# Sheet1.net
KiCad netlist of a schematic drawn in Altium Designer
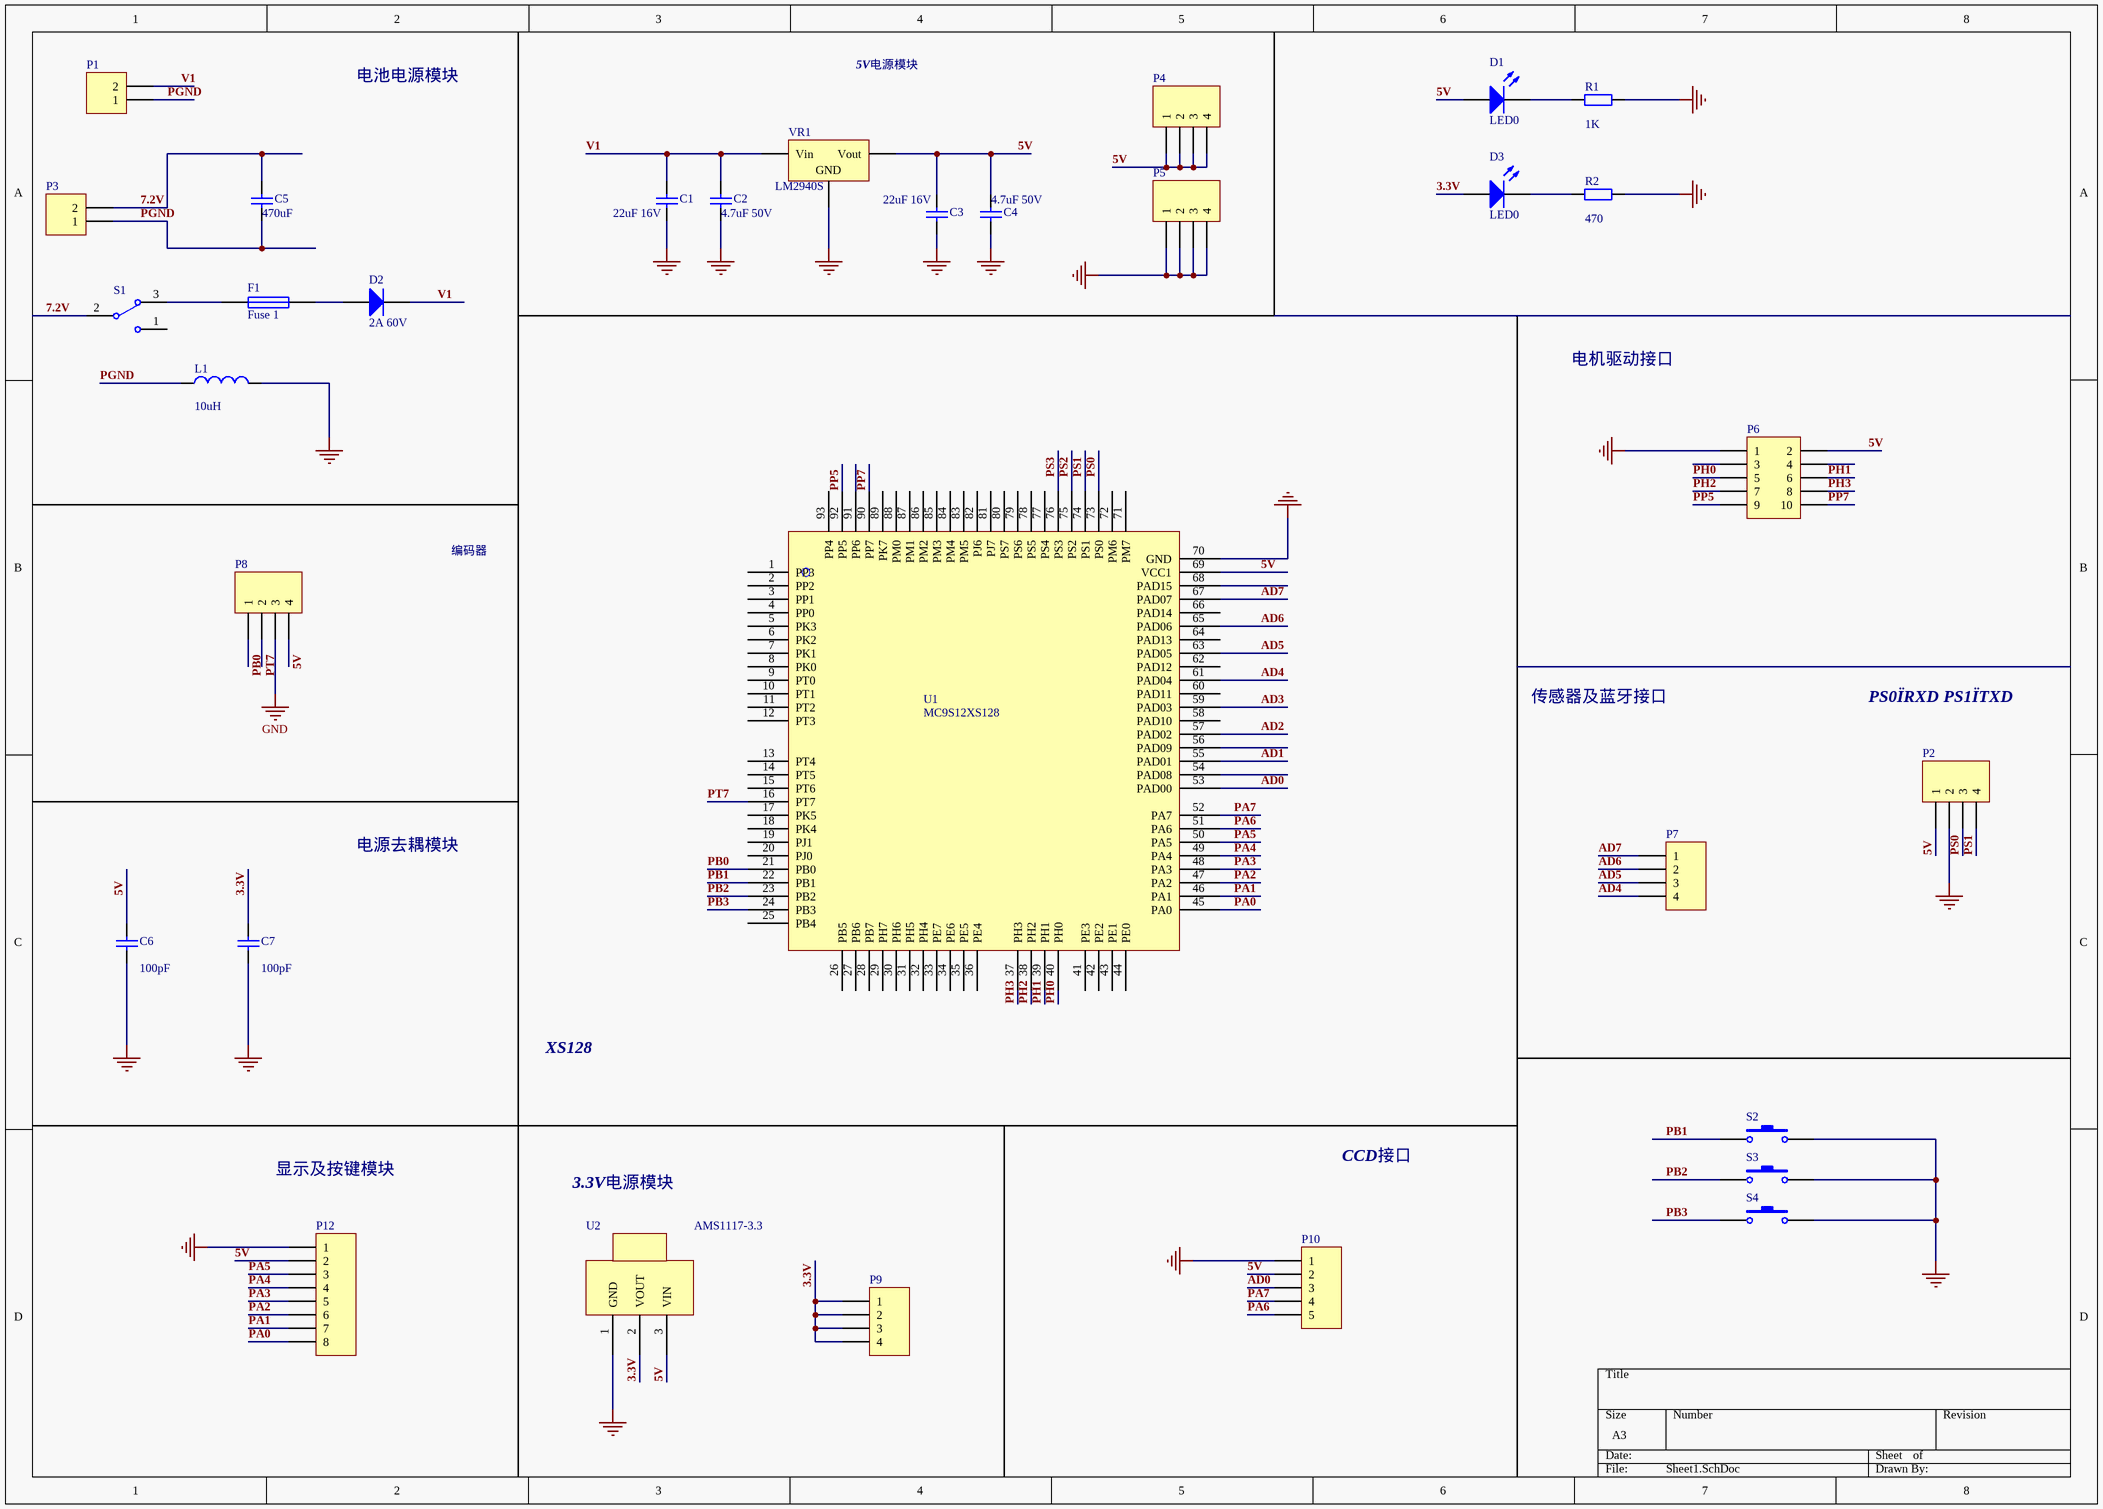
[diagram p0: Sheet1.SchDoc]

(export (version "E")
  (design (tool "Eeschema 10.0.6"))
  (components
    (comp (ref "C1")
      (value "22uF 16V")
      (footprint "22uF钽电容")
      (description "Capacitor")
      (fields (field (name "Comment") "Cap") (field (name "PUBLISHER") "Altium Limited"))
      (libsource (lib "Miscellaneous Devices") (part "Cap"))
    )
    (comp (ref "C2")
      (value "4.7uF 50V")
      (footprint "4.7UF钽电容")
      (description "Capacitor")
      (fields (field (name "Comment") "Cap") (field (name "PUBLISHER") "Altium Limited"))
      (libsource (lib "Miscellaneous Devices") (part "Cap"))
    )
    (comp (ref "C3")
      (value "22uF 16V")
      (footprint "22uF钽电容")
      (description "Capacitor")
      (fields (field (name "Comment") "Cap") (field (name "PUBLISHER") "Altium Limited"))
      (libsource (lib "Miscellaneous Devices") (part "Cap"))
    )
    (comp (ref "C4")
      (value "4.7uF 50V")
      (footprint "4.7UF钽电容")
      (description "Capacitor")
      (fields (field (name "Comment") "Cap") (field (name "PUBLISHER") "Altium Limited"))
      (libsource (lib "Miscellaneous Devices") (part "Cap"))
    )
    (comp (ref "C5")
      (value "470uF")
      (footprint "47UF钽电容")
      (description "Capacitor")
      (fields (field (name "Comment") "Cap") (field (name "PUBLISHER") "Altium Limited"))
      (libsource (lib "Miscellaneous Devices") (part "Cap"))
    )
    (comp (ref "C6")
      (value "100pF")
      (footprint "C0805")
      (description "Capacitor")
      (fields (field (name "Comment") "Cap") (field (name "PUBLISHER") "Altium Limited"))
      (libsource (lib "Miscellaneous Devices") (part "Cap"))
    )
    (comp (ref "C7")
      (value "100pF")
      (footprint "C0805")
      (description "Capacitor")
      (fields (field (name "Comment") "Cap") (field (name "PUBLISHER") "Altium Limited"))
      (libsource (lib "Miscellaneous Devices") (part "Cap"))
    )
    (comp (ref "D1")
      (value "LED0")
      (footprint "C0805")
      (description "Typical INFRARED GaAs LED")
      (fields (field (name "PUBLISHER") "Altium Limited"))
      (libsource (lib "Miscellaneous Devices") (part "LED0"))
    )
    (comp (ref "D2")
      (value "2A 60V")
      (footprint "FUSE")
      (description "1 Amp Fast Recovery Rectifier")
      (fields (field (name "PUBLISHER") "Altium Limited"))
      (libsource (lib "Miscellaneous Devices") (part "Diode 1N4934"))
    )
    (comp (ref "D3")
      (value "LED0")
      (footprint "C0805")
      (description "Typical INFRARED GaAs LED")
      (fields (field (name "PUBLISHER") "Altium Limited"))
      (libsource (lib "Miscellaneous Devices") (part "LED0"))
    )
    (comp (ref "F1")
      (value "Fuse 1")
      (footprint "FUSE")
      (description "2A")
      (fields (field (name "PUBLISHER") "Altium Limited"))
      (libsource (lib "Miscellaneous Devices") (part "Fuse 1"))
    )
    (comp (ref "L1")
      (value "10uH")
      (footprint "100uH")
      (description "Inductor")
      (fields (field (name "PUBLISHER") "Altium Limited"))
      (libsource (lib "Miscellaneous Devices") (part "Inductor"))
    )
    (comp (ref "P1")
      (value "Header 2H")
      (footprint "端子")
      (description "Header, 2-Pin, Right Angle")
      (fields (field (name "PUBLISHER") "Altium Limited"))
      (libsource (lib "Miscellaneous Connectors") (part "Header 2H"))
    )
    (comp (ref "P2")
      (value "Header 4")
      (footprint "HDR1X4")
      (description "Header, 4-Pin")
      (fields (field (name "PUBLISHER") "Altium Limited"))
      (libsource (lib "Miscellaneous Connectors") (part "Header 4"))
    )
    (comp (ref "P3")
      (value "Header 2H")
      (footprint "端子")
      (description "Header, 2-Pin, Right Angle")
      (fields (field (name "PUBLISHER") "Altium Limited"))
      (libsource (lib "Miscellaneous Connectors") (part "Header 2H"))
    )
    (comp (ref "P4")
      (value "Header 4")
      (footprint "HDR1X4")
      (description "Header, 4-Pin")
      (fields (field (name "PUBLISHER") "Altium Limited"))
      (libsource (lib "Miscellaneous Connectors") (part "Header 4"))
    )
    (comp (ref "P5")
      (value "Header 4")
      (footprint "HDR1X4")
      (description "Header, 4-Pin")
      (fields (field (name "PUBLISHER") "Altium Limited"))
      (libsource (lib "Miscellaneous Connectors") (part "Header 4"))
    )
    (comp (ref "P6")
      (value "Header 5X2")
      (footprint "HDR2X5")
      (description "Header, 5-Pin, Dual row")
      (fields (field (name "PUBLISHER") "Altium Limited"))
      (libsource (lib "Miscellaneous Connectors") (part "Header 5X2"))
    )
    (comp (ref "P7")
      (value "Header 4")
      (footprint "HDR1X4")
      (description "Header, 4-Pin")
      (fields (field (name "PUBLISHER") "Altium Limited"))
      (libsource (lib "") (part "Header 4_1"))
    )
    (comp (ref "P8")
      (value "Header 4")
      (footprint "HDR1X4")
      (description "Header, 4-Pin")
      (fields (field (name "PUBLISHER") "Altium Limited"))
      (libsource (lib "Miscellaneous Connectors") (part "Header 4"))
    )
    (comp (ref "P9")
      (value "Header 4")
      (footprint "HDR1X4")
      (description "Header, 4-Pin")
      (fields (field (name "PUBLISHER") "Altium Limited"))
      (libsource (lib "") (part "Header 4_1"))
    )
    (comp (ref "P10")
      (value "Header 5")
      (footprint "HDR1X5")
      (description "Header, 5-Pin")
      (fields (field (name "PUBLISHER") "Altium Limited"))
      (libsource (lib "Miscellaneous Connectors") (part "Header 5"))
    )
    (comp (ref "P12")
      (value "Header 8")
      (footprint "HDR1X8")
      (description "Header, 8-Pin")
      (fields (field (name "PUBLISHER") "Altium Limited"))
      (libsource (lib "Miscellaneous Connectors") (part "Header 8"))
    )
    (comp (ref "R1")
      (value "1K")
      (footprint "C0805")
      (description "Resistor")
      (fields (field (name "Comment") "Res2") (field (name "PUBLISHER") "Altium Limited"))
      (libsource (lib "Miscellaneous Devices") (part "Res2"))
    )
    (comp (ref "R2")
      (value "470")
      (footprint "C0805")
      (description "Resistor")
      (fields (field (name "Comment") "Res2") (field (name "PUBLISHER") "Altium Limited"))
      (libsource (lib "Miscellaneous Devices") (part "Res2"))
    )
    (comp (ref "S1")
      (value "SW-SPDT")
      (footprint "Rockey_Switch")
      (description "SPDT Subminiature Toggle Switch, Right Angle Mounting, Vertical Actuation")
      (fields (field (name "PUBLISHER") "Altium Limited"))
      (libsource (lib "Miscellaneous Devices") (part "SW-SPDT"))
    )
    (comp (ref "S2")
      (value "SW-PB")
      (footprint "白色按键")
      (description "Switch")
      (fields (field (name "PUBLISHER") "Altium Limited"))
      (libsource (lib "Miscellaneous Devices") (part "SW-PB"))
    )
    (comp (ref "S3")
      (value "SW-PB")
      (footprint "白色按键")
      (description "Switch")
      (fields (field (name "PUBLISHER") "Altium Limited"))
      (libsource (lib "Miscellaneous Devices") (part "SW-PB"))
    )
    (comp (ref "S4")
      (value "SW-PB")
      (footprint "白色按键")
      (description "Switch")
      (fields (field (name "PUBLISHER") "Altium Limited"))
      (libsource (lib "Miscellaneous Devices") (part "SW-PB"))
    )
    (comp (ref "U1") (value "MC9S12XS128") (footprint "XS128接口") (libsource (lib "*") (part "MC9S12XS128")))
    (comp (ref "U2") (value "AMS1117-3.3") (footprint "SOT223") (libsource (lib "*") (part "AMS1117-3.3")))
    (comp (ref "VR1")
      (value "LM2940S")
      (footprint "LM2940")
      (description "Voltage Regulator")
      (fields (field (name "PUBLISHER") "Altium Limited"))
      (libsource (lib "Miscellaneous Devices") (part "Volt Reg"))
    )
  )
  (nets
    (net (code "1") (name "/3.3V") (class "Default")
      (node (ref "C7") (pin "2") (pinfunction "2_2") (pintype "passive"))
      (node (ref "D3") (pin "1") (pinfunction "A_1") (pintype "passive"))
      (node (ref "P9") (pin "1") (pinfunction "1_1") (pintype "passive"))
      (node (ref "P9") (pin "2") (pinfunction "2_2") (pintype "passive"))
      (node (ref "P9") (pin "3") (pinfunction "3_3") (pintype "passive"))
      (node (ref "P9") (pin "4") (pinfunction "4_4") (pintype "passive"))
      (node (ref "U2") (pin "2") (pinfunction "VOUT_2") (pintype "passive"))
    )
    (net (code "2") (name "/5V") (class "Default")
      (node (ref "C3") (pin "2") (pinfunction "2_2") (pintype "passive"))
      (node (ref "C4") (pin "2") (pinfunction "2_2") (pintype "passive"))
      (node (ref "C6") (pin "2") (pinfunction "2_2") (pintype "passive"))
      (node (ref "D1") (pin "1") (pinfunction "A_1") (pintype "passive"))
      (node (ref "P10") (pin "2") (pinfunction "2_2") (pintype "passive"))
      (node (ref "P12") (pin "2") (pinfunction "2_2") (pintype "passive"))
      (node (ref "P2") (pin "1") (pinfunction "1_1") (pintype "passive"))
      (node (ref "P4") (pin "1") (pinfunction "1_1") (pintype "passive"))
      (node (ref "P4") (pin "2") (pinfunction "2_2") (pintype "passive"))
      (node (ref "P4") (pin "3") (pinfunction "3_3") (pintype "passive"))
      (node (ref "P4") (pin "4") (pinfunction "4_4") (pintype "passive"))
      (node (ref "P6") (pin "2") (pinfunction "2_2") (pintype "passive"))
      (node (ref "P8") (pin "4") (pinfunction "4_4") (pintype "passive"))
      (node (ref "U1") (pin "69") (pinfunction "VCC1_69") (pintype "passive"))
      (node (ref "U2") (pin "3") (pinfunction "VIN_3") (pintype "passive"))
      (node (ref "VR1") (pin "3") (pinfunction "Vout_3") (pintype "passive"))
    )
    (net (code "3") (name "/7.2V") (class "Default")
      (node (ref "C5") (pin "2") (pinfunction "2_2") (pintype "passive"))
      (node (ref "P3") (pin "2") (pinfunction "2_2") (pintype "passive"))
      (node (ref "S1") (pin "2") (pinfunction "2_2") (pintype "passive"))
    )
    (net (code "4") (name "/AD0") (class "Default")
      (node (ref "P10") (pin "3") (pinfunction "3_3") (pintype "passive"))
      (node (ref "U1") (pin "53") (pinfunction "PAD00_53") (pintype "passive"))
    )
    (net (code "5") (name "/AD1") (class "Default")
      (node (ref "U1") (pin "55") (pinfunction "PAD01_55") (pintype "passive"))
    )
    (net (code "6") (name "/AD2") (class "Default")
      (node (ref "U1") (pin "57") (pinfunction "PAD02_57") (pintype "passive"))
    )
    (net (code "7") (name "/AD3") (class "Default")
      (node (ref "U1") (pin "59") (pinfunction "PAD03_59") (pintype "passive"))
    )
    (net (code "8") (name "/AD4") (class "Default")
      (node (ref "P7") (pin "4") (pinfunction "4_4") (pintype "passive"))
      (node (ref "U1") (pin "61") (pinfunction "PAD04_61") (pintype "passive"))
    )
    (net (code "9") (name "/AD5") (class "Default")
      (node (ref "P7") (pin "3") (pinfunction "3_3") (pintype "passive"))
      (node (ref "U1") (pin "63") (pinfunction "PAD05_63") (pintype "passive"))
    )
    (net (code "10") (name "/AD6") (class "Default")
      (node (ref "P7") (pin "2") (pinfunction "2_2") (pintype "passive"))
      (node (ref "U1") (pin "65") (pinfunction "PAD06_65") (pintype "passive"))
    )
    (net (code "11") (name "/AD7") (class "Default")
      (node (ref "P7") (pin "1") (pinfunction "1_1") (pintype "passive"))
      (node (ref "U1") (pin "67") (pinfunction "PAD07_67") (pintype "passive"))
    )
    (net (code "12") (name "/PA0") (class "Default")
      (node (ref "P12") (pin "8") (pinfunction "8_8") (pintype "passive"))
      (node (ref "U1") (pin "45") (pinfunction "PA0_45") (pintype "passive"))
    )
    (net (code "13") (name "/PA1") (class "Default")
      (node (ref "P12") (pin "7") (pinfunction "7_7") (pintype "passive"))
      (node (ref "U1") (pin "46") (pinfunction "PA1_46") (pintype "passive"))
    )
    (net (code "14") (name "/PA2") (class "Default")
      (node (ref "P12") (pin "6") (pinfunction "6_6") (pintype "passive"))
      (node (ref "U1") (pin "47") (pinfunction "PA2_47") (pintype "passive"))
    )
    (net (code "15") (name "/PA3") (class "Default")
      (node (ref "P12") (pin "5") (pinfunction "5_5") (pintype "passive"))
      (node (ref "U1") (pin "48") (pinfunction "PA3_48") (pintype "passive"))
    )
    (net (code "16") (name "/PA4") (class "Default")
      (node (ref "P12") (pin "4") (pinfunction "4_4") (pintype "passive"))
      (node (ref "U1") (pin "49") (pinfunction "PA4_49") (pintype "passive"))
    )
    (net (code "17") (name "/PA5") (class "Default")
      (node (ref "P12") (pin "3") (pinfunction "3_3") (pintype "passive"))
      (node (ref "U1") (pin "50") (pinfunction "PA5_50") (pintype "passive"))
    )
    (net (code "18") (name "/PA6") (class "Default")
      (node (ref "P10") (pin "5") (pinfunction "5_5") (pintype "passive"))
      (node (ref "U1") (pin "51") (pinfunction "PA6_51") (pintype "passive"))
    )
    (net (code "19") (name "/PA7") (class "Default")
      (node (ref "P10") (pin "4") (pinfunction "4_4") (pintype "passive"))
      (node (ref "U1") (pin "52") (pinfunction "PA7_52") (pintype "passive"))
    )
    (net (code "20") (name "/PB0") (class "Default")
      (node (ref "P8") (pin "1") (pinfunction "1_1") (pintype "passive"))
      (node (ref "U1") (pin "21") (pinfunction "PB0_21") (pintype "passive"))
    )
    (net (code "21") (name "/PB1") (class "Default")
      (node (ref "S2") (pin "1") (pinfunction "1_1") (pintype "passive"))
      (node (ref "U1") (pin "22") (pinfunction "PB1_22") (pintype "passive"))
    )
    (net (code "22") (name "/PB2") (class "Default")
      (node (ref "S3") (pin "1") (pinfunction "1_1") (pintype "passive"))
      (node (ref "U1") (pin "23") (pinfunction "PB2_23") (pintype "passive"))
    )
    (net (code "23") (name "/PB3") (class "Default")
      (node (ref "S4") (pin "1") (pinfunction "1_1") (pintype "passive"))
      (node (ref "U1") (pin "24") (pinfunction "PB3_24") (pintype "passive"))
    )
    (net (code "24") (name "/PGND") (class "Default")
      (node (ref "C5") (pin "1") (pinfunction "1_1") (pintype "passive"))
      (node (ref "L1") (pin "1") (pinfunction "1_1") (pintype "passive"))
      (node (ref "P1") (pin "1") (pinfunction "1_1") (pintype "passive"))
      (node (ref "P3") (pin "1") (pinfunction "1_1") (pintype "passive"))
    )
    (net (code "25") (name "/PH0") (class "Default")
      (node (ref "P6") (pin "5") (pinfunction "5_5") (pintype "passive"))
      (node (ref "U1") (pin "40") (pinfunction "PH0_40") (pintype "passive"))
    )
    (net (code "26") (name "/PH1") (class "Default")
      (node (ref "P6") (pin "6") (pinfunction "6_6") (pintype "passive"))
      (node (ref "U1") (pin "39") (pinfunction "PH1_39") (pintype "passive"))
    )
    (net (code "27") (name "/PH2") (class "Default")
      (node (ref "P6") (pin "7") (pinfunction "7_7") (pintype "passive"))
      (node (ref "U1") (pin "38") (pinfunction "PH2_38") (pintype "passive"))
    )
    (net (code "28") (name "/PH3") (class "Default")
      (node (ref "P6") (pin "8") (pinfunction "8_8") (pintype "passive"))
      (node (ref "U1") (pin "37") (pinfunction "PH3_37") (pintype "passive"))
    )
    (net (code "29") (name "/PP5") (class "Default")
      (node (ref "P6") (pin "9") (pinfunction "9_9") (pintype "passive"))
      (node (ref "U1") (pin "92") (pinfunction "PP5_92") (pintype "passive"))
    )
    (net (code "30") (name "/PP7") (class "Default")
      (node (ref "P6") (pin "10") (pinfunction "10_10") (pintype "passive"))
      (node (ref "U1") (pin "90") (pinfunction "PP7_90") (pintype "passive"))
    )
    (net (code "31") (name "/PS0") (class "Default")
      (node (ref "P2") (pin "3") (pinfunction "3_3") (pintype "passive"))
      (node (ref "U1") (pin "73") (pinfunction "PS0_73") (pintype "passive"))
    )
    (net (code "32") (name "/PS1") (class "Default")
      (node (ref "P2") (pin "4") (pinfunction "4_4") (pintype "passive"))
      (node (ref "U1") (pin "74") (pinfunction "PS1_74") (pintype "passive"))
    )
    (net (code "33") (name "/PS2") (class "Default")
      (node (ref "U1") (pin "75") (pinfunction "PS2_75") (pintype "passive"))
    )
    (net (code "34") (name "/PS3") (class "Default")
      (node (ref "U1") (pin "76") (pinfunction "PS3_76") (pintype "passive"))
    )
    (net (code "35") (name "/PT7") (class "Default")
      (node (ref "P8") (pin "2") (pinfunction "2_2") (pintype "passive"))
      (node (ref "U1") (pin "16") (pinfunction "PT7_16") (pintype "passive"))
    )
    (net (code "36") (name "/V1") (class "Default")
      (node (ref "C1") (pin "2") (pinfunction "2_2") (pintype "passive"))
      (node (ref "C2") (pin "2") (pinfunction "2_2") (pintype "passive"))
      (node (ref "D2") (pin "2") (pinfunction "K_2") (pintype "passive"))
      (node (ref "P1") (pin "2") (pinfunction "2_2") (pintype "passive"))
      (node (ref "VR1") (pin "1") (pinfunction "Vin_1") (pintype "passive"))
    )
    (net (code "37") (name "GND") (class "Default")
      (node (ref "C1") (pin "1") (pinfunction "1_1") (pintype "passive"))
      (node (ref "C2") (pin "1") (pinfunction "1_1") (pintype "passive"))
      (node (ref "C3") (pin "1") (pinfunction "1_1") (pintype "passive"))
      (node (ref "C4") (pin "1") (pinfunction "1_1") (pintype "passive"))
      (node (ref "C6") (pin "1") (pinfunction "1_1") (pintype "passive"))
      (node (ref "C7") (pin "1") (pinfunction "1_1") (pintype "passive"))
      (node (ref "L1") (pin "2") (pinfunction "2_2") (pintype "passive"))
      (node (ref "P10") (pin "1") (pinfunction "1_1") (pintype "passive"))
      (node (ref "P12") (pin "1") (pinfunction "1_1") (pintype "passive"))
      (node (ref "P2") (pin "2") (pinfunction "2_2") (pintype "passive"))
      (node (ref "P5") (pin "1") (pinfunction "1_1") (pintype "passive"))
      (node (ref "P5") (pin "2") (pinfunction "2_2") (pintype "passive"))
      (node (ref "P5") (pin "3") (pinfunction "3_3") (pintype "passive"))
      (node (ref "P5") (pin "4") (pinfunction "4_4") (pintype "passive"))
      (node (ref "P6") (pin "1") (pinfunction "1_1") (pintype "passive"))
      (node (ref "P8") (pin "3") (pinfunction "3_3") (pintype "passive"))
      (node (ref "R1") (pin "2") (pinfunction "2_2") (pintype "passive"))
      (node (ref "R2") (pin "2") (pinfunction "2_2") (pintype "passive"))
      (node (ref "S2") (pin "2") (pinfunction "2_2") (pintype "passive"))
      (node (ref "S3") (pin "2") (pinfunction "2_2") (pintype "passive"))
      (node (ref "S4") (pin "2") (pinfunction "2_2") (pintype "passive"))
      (node (ref "U1") (pin "70") (pinfunction "GND_70") (pintype "passive"))
      (node (ref "U2") (pin "1") (pinfunction "GND_1") (pintype "passive"))
      (node (ref "VR1") (pin "2") (pinfunction "GND_2") (pintype "passive"))
    )
    (net (code "38") (name "Net-(D1-K)") (class "Default")
      (node (ref "D1") (pin "2") (pinfunction "K_2") (pintype "passive"))
      (node (ref "R1") (pin "1") (pinfunction "1_1") (pintype "passive"))
    )
    (net (code "39") (name "Net-(D2-A)") (class "Default")
      (node (ref "D2") (pin "1") (pinfunction "A_1") (pintype "passive"))
      (node (ref "F1") (pin "2") (pinfunction "2_2") (pintype "passive"))
    )
    (net (code "40") (name "Net-(D3-K)") (class "Default")
      (node (ref "D3") (pin "2") (pinfunction "K_2") (pintype "passive"))
      (node (ref "R2") (pin "1") (pinfunction "1_1") (pintype "passive"))
    )
    (net (code "41") (name "Net-(F1-Pad1)") (class "Default")
      (node (ref "F1") (pin "1") (pinfunction "1_1") (pintype "passive"))
      (node (ref "S1") (pin "3") (pinfunction "3_3") (pintype "passive"))
    )
    (net (code "42") (name "unconnected-(P6-Pad3)") (class "Default")
      (node (ref "P6") (pin "3") (pinfunction "3_3") (pintype "passive"))
    )
    (net (code "43") (name "unconnected-(P6-Pad4)") (class "Default")
      (node (ref "P6") (pin "4") (pinfunction "4_4") (pintype "passive"))
    )
    (net (code "44") (name "unconnected-(S1-Pad1)") (class "Default")
      (node (ref "S1") (pin "1") (pinfunction "1_1") (pintype "passive"))
    )
    (net (code "45") (name "unconnected-(U1-PAD08-Pad54)") (class "Default")
      (node (ref "U1") (pin "54") (pinfunction "PAD08_54") (pintype "passive"))
    )
    (net (code "46") (name "unconnected-(U1-PAD09-Pad56)") (class "Default")
      (node (ref "U1") (pin "56") (pinfunction "PAD09_56") (pintype "passive"))
    )
    (net (code "47") (name "unconnected-(U1-PAD10-Pad58)") (class "Default")
      (node (ref "U1") (pin "58") (pinfunction "PAD10_58") (pintype "passive"))
    )
    (net (code "48") (name "unconnected-(U1-PAD11-Pad60)") (class "Default")
      (node (ref "U1") (pin "60") (pinfunction "PAD11_60") (pintype "passive"))
    )
    (net (code "49") (name "unconnected-(U1-PAD12-Pad62)") (class "Default")
      (node (ref "U1") (pin "62") (pinfunction "PAD12_62") (pintype "passive"))
    )
    (net (code "50") (name "unconnected-(U1-PAD13-Pad64)") (class "Default")
      (node (ref "U1") (pin "64") (pinfunction "PAD13_64") (pintype "passive"))
    )
    (net (code "51") (name "unconnected-(U1-PAD14-Pad66)") (class "Default")
      (node (ref "U1") (pin "66") (pinfunction "PAD14_66") (pintype "passive"))
    )
    (net (code "52") (name "unconnected-(U1-PAD15-Pad68)") (class "Default")
      (node (ref "U1") (pin "68") (pinfunction "PAD15_68") (pintype "passive"))
    )
    (net (code "53") (name "unconnected-(U1-PB4-Pad25)") (class "Default")
      (node (ref "U1") (pin "25") (pinfunction "PB4_25") (pintype "passive"))
    )
    (net (code "54") (name "unconnected-(U1-PB5-Pad26)") (class "Default")
      (node (ref "U1") (pin "26") (pinfunction "PB5_26") (pintype "passive"))
    )
    (net (code "55") (name "unconnected-(U1-PB6-Pad27)") (class "Default")
      (node (ref "U1") (pin "27") (pinfunction "PB6_27") (pintype "passive"))
    )
    (net (code "56") (name "unconnected-(U1-PB7-Pad28)") (class "Default")
      (node (ref "U1") (pin "28") (pinfunction "PB7_28") (pintype "passive"))
    )
    (net (code "57") (name "unconnected-(U1-PE0-Pad44)") (class "Default")
      (node (ref "U1") (pin "44") (pinfunction "PE0_44") (pintype "passive"))
    )
    (net (code "58") (name "unconnected-(U1-PE1-Pad43)") (class "Default")
      (node (ref "U1") (pin "43") (pinfunction "PE1_43") (pintype "passive"))
    )
    (net (code "59") (name "unconnected-(U1-PE2-Pad42)") (class "Default")
      (node (ref "U1") (pin "42") (pinfunction "PE2_42") (pintype "passive"))
    )
    (net (code "60") (name "unconnected-(U1-PE3-Pad41)") (class "Default")
      (node (ref "U1") (pin "41") (pinfunction "PE3_41") (pintype "passive"))
    )
    (net (code "61") (name "unconnected-(U1-PE4-Pad36)") (class "Default")
      (node (ref "U1") (pin "36") (pinfunction "PE4_36") (pintype "passive"))
    )
    (net (code "62") (name "unconnected-(U1-PE5-Pad35)") (class "Default")
      (node (ref "U1") (pin "35") (pinfunction "PE5_35") (pintype "passive"))
    )
    (net (code "63") (name "unconnected-(U1-PE6-Pad34)") (class "Default")
      (node (ref "U1") (pin "34") (pinfunction "PE6_34") (pintype "passive"))
    )
    (net (code "64") (name "unconnected-(U1-PE7-Pad33)") (class "Default")
      (node (ref "U1") (pin "33") (pinfunction "PE7_33") (pintype "passive"))
    )
    (net (code "65") (name "unconnected-(U1-PH4-Pad32)") (class "Default")
      (node (ref "U1") (pin "32") (pinfunction "PH4_32") (pintype "passive"))
    )
    (net (code "66") (name "unconnected-(U1-PH5-Pad31)") (class "Default")
      (node (ref "U1") (pin "31") (pinfunction "PH5_31") (pintype "passive"))
    )
    (net (code "67") (name "unconnected-(U1-PH6-Pad30)") (class "Default")
      (node (ref "U1") (pin "30") (pinfunction "PH6_30") (pintype "passive"))
    )
    (net (code "68") (name "unconnected-(U1-PH7-Pad29)") (class "Default")
      (node (ref "U1") (pin "29") (pinfunction "PH7_29") (pintype "passive"))
    )
    (net (code "69") (name "unconnected-(U1-PJ0-Pad20)") (class "Default")
      (node (ref "U1") (pin "20") (pinfunction "PJ0_20") (pintype "passive"))
    )
    (net (code "70") (name "unconnected-(U1-PJ1-Pad19)") (class "Default")
      (node (ref "U1") (pin "19") (pinfunction "PJ1_19") (pintype "passive"))
    )
    (net (code "71") (name "unconnected-(U1-PJ6-Pad82)") (class "Default")
      (node (ref "U1") (pin "82") (pinfunction "PJ6_82") (pintype "passive"))
    )
    (net (code "72") (name "unconnected-(U1-PJ7-Pad81)") (class "Default")
      (node (ref "U1") (pin "81") (pinfunction "PJ7_81") (pintype "passive"))
    )
    (net (code "73") (name "unconnected-(U1-PK0-Pad8)") (class "Default")
      (node (ref "U1") (pin "8") (pinfunction "PK0_8") (pintype "passive"))
    )
    (net (code "74") (name "unconnected-(U1-PK1-Pad7)") (class "Default")
      (node (ref "U1") (pin "7") (pinfunction "PK1_7") (pintype "passive"))
    )
    (net (code "75") (name "unconnected-(U1-PK2-Pad6)") (class "Default")
      (node (ref "U1") (pin "6") (pinfunction "PK2_6") (pintype "passive"))
    )
    (net (code "76") (name "unconnected-(U1-PK3-Pad5)") (class "Default")
      (node (ref "U1") (pin "5") (pinfunction "PK3_5") (pintype "passive"))
    )
    (net (code "77") (name "unconnected-(U1-PK4-Pad18)") (class "Default")
      (node (ref "U1") (pin "18") (pinfunction "PK4_18") (pintype "passive"))
    )
    (net (code "78") (name "unconnected-(U1-PK5-Pad17)") (class "Default")
      (node (ref "U1") (pin "17") (pinfunction "PK5_17") (pintype "passive"))
    )
    (net (code "79") (name "unconnected-(U1-PK7-Pad89)") (class "Default")
      (node (ref "U1") (pin "89") (pinfunction "PK7_89") (pintype "passive"))
    )
    (net (code "80") (name "unconnected-(U1-PM0-Pad88)") (class "Default")
      (node (ref "U1") (pin "88") (pinfunction "PM0_88") (pintype "passive"))
    )
    (net (code "81") (name "unconnected-(U1-PM1-Pad87)") (class "Default")
      (node (ref "U1") (pin "87") (pinfunction "PM1_87") (pintype "passive"))
    )
    (net (code "82") (name "unconnected-(U1-PM2-Pad86)") (class "Default")
      (node (ref "U1") (pin "86") (pinfunction "PM2_86") (pintype "passive"))
    )
    (net (code "83") (name "unconnected-(U1-PM3-Pad85)") (class "Default")
      (node (ref "U1") (pin "85") (pinfunction "PM3_85") (pintype "passive"))
    )
    (net (code "84") (name "unconnected-(U1-PM4-Pad84)") (class "Default")
      (node (ref "U1") (pin "84") (pinfunction "PM4_84") (pintype "passive"))
    )
    (net (code "85") (name "unconnected-(U1-PM5-Pad83)") (class "Default")
      (node (ref "U1") (pin "83") (pinfunction "PM5_83") (pintype "passive"))
    )
    (net (code "86") (name "unconnected-(U1-PM6-Pad72)") (class "Default")
      (node (ref "U1") (pin "72") (pinfunction "PM6_72") (pintype "passive"))
    )
    (net (code "87") (name "unconnected-(U1-PM7-Pad71)") (class "Default")
      (node (ref "U1") (pin "71") (pinfunction "PM7_71") (pintype "passive"))
    )
    (net (code "88") (name "unconnected-(U1-PP0-Pad4)") (class "Default")
      (node (ref "U1") (pin "4") (pinfunction "PP0_4") (pintype "passive"))
    )
    (net (code "89") (name "unconnected-(U1-PP1-Pad3)") (class "Default")
      (node (ref "U1") (pin "3") (pinfunction "PP1_3") (pintype "passive"))
    )
    (net (code "90") (name "unconnected-(U1-PP2-Pad2)") (class "Default")
      (node (ref "U1") (pin "2") (pinfunction "PP2_2") (pintype "passive"))
    )
    (net (code "91") (name "unconnected-(U1-PP3-Pad1)") (class "Default")
      (node (ref "U1") (pin "1") (pinfunction "PP3_1") (pintype "passive"))
    )
    (net (code "92") (name "unconnected-(U1-PP4-Pad93)") (class "Default")
      (node (ref "U1") (pin "93") (pinfunction "PP4_93") (pintype "passive"))
    )
    (net (code "93") (name "unconnected-(U1-PP6-Pad91)") (class "Default")
      (node (ref "U1") (pin "91") (pinfunction "PP6_91") (pintype "passive"))
    )
    (net (code "94") (name "unconnected-(U1-PS4-Pad77)") (class "Default")
      (node (ref "U1") (pin "77") (pinfunction "PS4_77") (pintype "passive"))
    )
    (net (code "95") (name "unconnected-(U1-PS5-Pad78)") (class "Default")
      (node (ref "U1") (pin "78") (pinfunction "PS5_78") (pintype "passive"))
    )
    (net (code "96") (name "unconnected-(U1-PS6-Pad79)") (class "Default")
      (node (ref "U1") (pin "79") (pinfunction "PS6_79") (pintype "passive"))
    )
    (net (code "97") (name "unconnected-(U1-PS7-Pad80)") (class "Default")
      (node (ref "U1") (pin "80") (pinfunction "PS7_80") (pintype "passive"))
    )
    (net (code "98") (name "unconnected-(U1-PT0-Pad9)") (class "Default")
      (node (ref "U1") (pin "9") (pinfunction "PT0_9") (pintype "passive"))
    )
    (net (code "99") (name "unconnected-(U1-PT1-Pad10)") (class "Default")
      (node (ref "U1") (pin "10") (pinfunction "PT1_10") (pintype "passive"))
    )
    (net (code "100") (name "unconnected-(U1-PT2-Pad11)") (class "Default")
      (node (ref "U1") (pin "11") (pinfunction "PT2_11") (pintype "passive"))
    )
    (net (code "101") (name "unconnected-(U1-PT3-Pad12)") (class "Default")
      (node (ref "U1") (pin "12") (pinfunction "PT3_12") (pintype "passive"))
    )
    (net (code "102") (name "unconnected-(U1-PT4-Pad13)") (class "Default")
      (node (ref "U1") (pin "13") (pinfunction "PT4_13") (pintype "passive"))
    )
    (net (code "103") (name "unconnected-(U1-PT5-Pad14)") (class "Default")
      (node (ref "U1") (pin "14") (pinfunction "PT5_14") (pintype "passive"))
    )
    (net (code "104") (name "unconnected-(U1-PT6-Pad15)") (class "Default")
      (node (ref "U1") (pin "15") (pinfunction "PT6_15") (pintype "passive"))
    )
  )
)
